# SW6106_Demo_board.net
KiCad netlist of a schematic drawn in Altium Designer
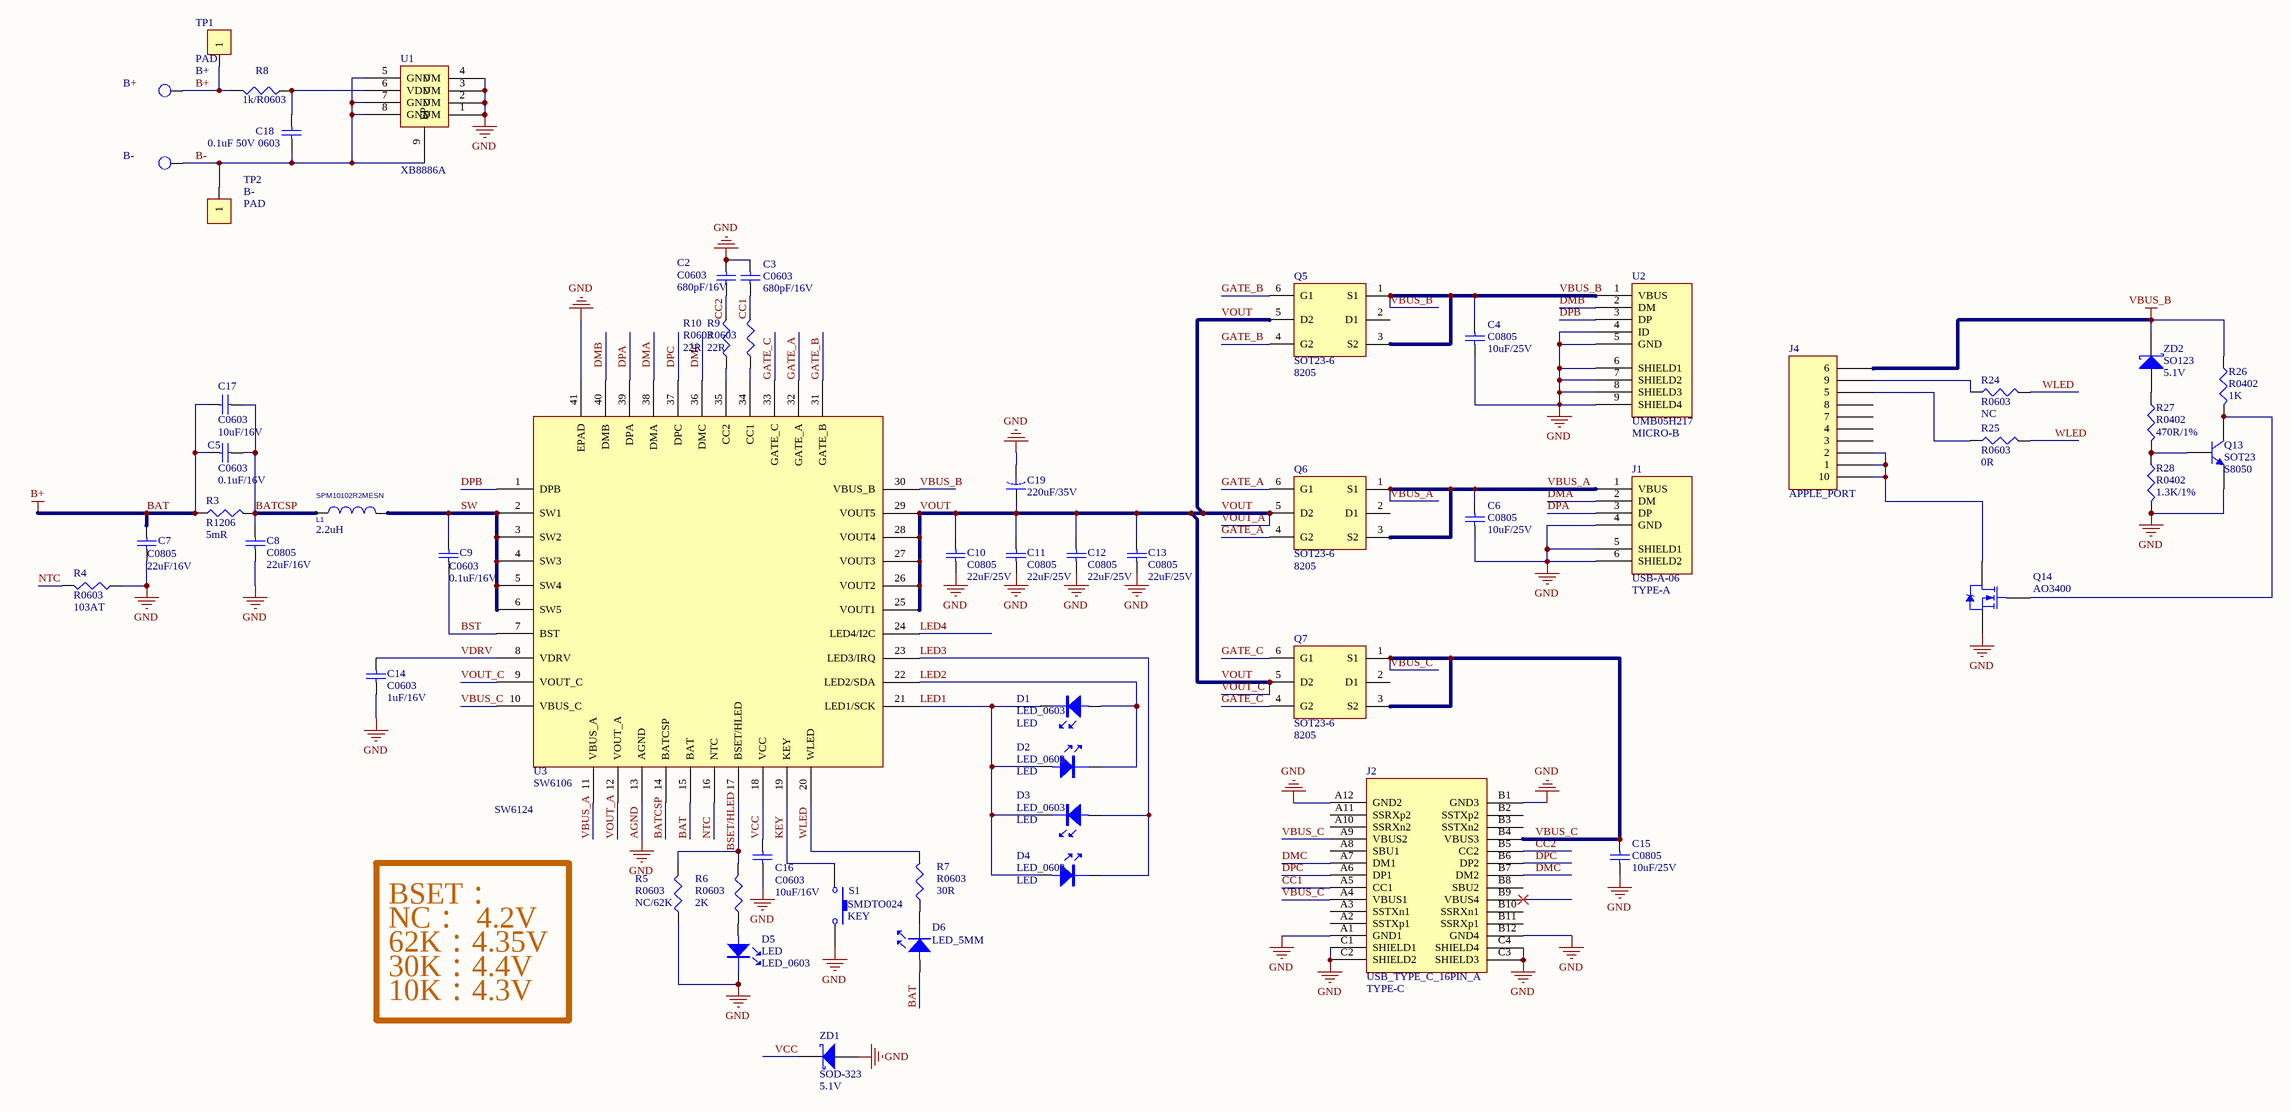
[diagram p0: SW6106 Demo board.SchDoc]

(export (version "E")
  (design (tool "Eeschema 10.0.6"))
  (components
    (comp (ref "B+") (value "PDA") (footprint "PAD") (libsource (lib "ZYX") (part "PDA")))
    (comp (ref "B-") (value "PDA") (footprint "PAD") (libsource (lib "ZYX") (part "PDA")))
    (comp (ref "C2")
      (value "C0603")
      (footprint "C0603")
      (description "Capacitor")
      (fields (field (name "ALTIUM_VALUE") "680pF/16V") (field (name "PUBLISHER") "Altium Limited"))
      (libsource (lib "*") (part "CAP0603"))
    )
    (comp (ref "C3")
      (value "C0603")
      (footprint "C0603")
      (description "Capacitor")
      (fields (field (name "ALTIUM_VALUE") "680pF/16V") (field (name "PUBLISHER") "Altium Limited"))
      (libsource (lib "*") (part "CAP0603"))
    )
    (comp (ref "C4")
      (value "C0805")
      (footprint "C0805")
      (description "Capacitor")
      (fields (field (name "ALTIUM_VALUE") "10uF/25V") (field (name "PUBLISHER") "Altium Limited"))
      (libsource (lib "*") (part "CAP0603"))
    )
    (comp (ref "C5")
      (value "C0603")
      (footprint "C0603")
      (description "Capacitor")
      (fields (field (name "ALTIUM_VALUE") "0.1uF/16V") (field (name "PUBLISHER") "Altium Limited"))
      (libsource (lib "*") (part "CAP0603"))
    )
    (comp (ref "C6")
      (value "C0805")
      (footprint "C0805")
      (description "Capacitor")
      (fields (field (name "ALTIUM_VALUE") "10uF/25V") (field (name "PUBLISHER") "Altium Limited"))
      (libsource (lib "*") (part "CAP0603"))
    )
    (comp (ref "C7")
      (value "C0805")
      (footprint "C0805")
      (description "Capacitor")
      (fields (field (name "ALTIUM_VALUE") "22uF/16V") (field (name "PUBLISHER") "Altium Limited"))
      (libsource (lib "*") (part "CAP0805"))
    )
    (comp (ref "C8")
      (value "C0805")
      (footprint "C0805")
      (description "Capacitor")
      (fields (field (name "ALTIUM_VALUE") "22uF/16V") (field (name "PUBLISHER") "Altium Limited"))
      (libsource (lib "*") (part "CAP0805"))
    )
    (comp (ref "C9")
      (value "C0603")
      (footprint "C0603")
      (description "Capacitor")
      (fields (field (name "ALTIUM_VALUE") "0.1uF/16V") (field (name "PUBLISHER") "Altium Limited"))
      (libsource (lib "*") (part "CAP0603"))
    )
    (comp (ref "C10")
      (value "C0805")
      (footprint "C0805")
      (description "Capacitor")
      (fields (field (name "ALTIUM_VALUE") "22uF/25V") (field (name "PUBLISHER") "Altium Limited"))
      (libsource (lib "*") (part "CAP0805"))
    )
    (comp (ref "C11")
      (value "C0805")
      (footprint "C0805")
      (description "Capacitor")
      (fields (field (name "ALTIUM_VALUE") "22uF/25V") (field (name "PUBLISHER") "Altium Limited"))
      (libsource (lib "*") (part "CAP0805"))
    )
    (comp (ref "C12")
      (value "C0805")
      (footprint "C0805")
      (description "Capacitor")
      (fields (field (name "ALTIUM_VALUE") "22uF/25V") (field (name "PUBLISHER") "Altium Limited"))
      (libsource (lib "*") (part "CAP0805"))
    )
    (comp (ref "C13")
      (value "C0805")
      (footprint "C0805")
      (description "Capacitor")
      (fields (field (name "ALTIUM_VALUE") "22uF/25V") (field (name "PUBLISHER") "Altium Limited"))
      (libsource (lib "*") (part "CAP0805"))
    )
    (comp (ref "C14")
      (value "C0603")
      (footprint "C0603")
      (description "Capacitor")
      (fields (field (name "ALTIUM_VALUE") "1uF/16V") (field (name "PUBLISHER") "Altium Limited"))
      (libsource (lib "*") (part "CAP0603"))
    )
    (comp (ref "C15")
      (value "C0805")
      (footprint "C0805")
      (description "Capacitor")
      (fields (field (name "ALTIUM_VALUE") "10uF/25V") (field (name "PUBLISHER") "Altium Limited"))
      (libsource (lib "*") (part "CAP0603"))
    )
    (comp (ref "C16")
      (value "C0603")
      (footprint "C0603")
      (description "Capacitor")
      (fields (field (name "ALTIUM_VALUE") "10uF/16V") (field (name "PUBLISHER") "Altium Limited"))
      (libsource (lib "*") (part "CAP0603"))
    )
    (comp (ref "C17")
      (value "C0603")
      (footprint "C0603")
      (description "Capacitor")
      (fields (field (name "ALTIUM_VALUE") "10uF/16V") (field (name "PUBLISHER") "Altium Limited"))
      (libsource (lib "*") (part "CAP0603"))
    )
    (comp (ref "C18") (value "0.1uF 50V 0603") (footprint "LIB:C0402") (libsource (lib "ZYX") (part "Cap")))
    (comp (ref "C19")
      (value "220uF/35V")
      (footprint "Cap  ( E )  6.5 * 12.0  Erect")
      (description "Electroytic Capacitor, 100uF/35V, ±20%, 105℃，Φ 6.5 * 12.0 mm")
      (fields (field (name "Comment") "E - Cap") (field (name "PUBLISHER") "Altium Limited"))
      (libsource (lib "D-lib") (part "E - Cap"))
    )
    (comp (ref "D1") (value "LED") (footprint "LED_0603") (libsource (lib "*") (part "LED")))
    (comp (ref "D2") (value "LED") (footprint "LED_0603") (libsource (lib "*") (part "LED")))
    (comp (ref "D3") (value "LED") (footprint "LED_0603") (libsource (lib "*") (part "LED")))
    (comp (ref "D4") (value "LED") (footprint "LED_0603") (libsource (lib "*") (part "LED")))
    (comp (ref "D5") (value "LED") (footprint "LED_0603") (libsource (lib "*") (part "LED")))
    (comp (ref "D6")
      (value "LED_5MM")
      (footprint "LED_5MM")
      (fields (field (name "FOOTPRINF") "LED_5MM"))
      (libsource (lib "*") (part "LED"))
    )
    (comp (ref "J1")
      (value "TYPE-A")
      (footprint "USB-A-06")
      (fields (field (name "FOOTPRINF") "USB-A-06") (field (name "Comment") "TYPE-A-1"))
      (libsource (lib "*") (part "TYPE-A-1"))
    )
    (comp (ref "J2") (value "TYPE-C") (footprint "USB_TYPE_C_16PIN_A") (libsource (lib "*") (part "TYPE-C")))
    (comp (ref "J4")
      (value "APPLE_PORT")
      (footprint "Lightning")
      (libsource (lib "TEST") (part "APPLE_PORT"))
    )
    (comp (ref "L1")
      (value "SPM10102R2MESN")
      (footprint "INDUCTOR_SPM1010")
      (fields (field (name "ALTIUM_VALUE") "2.2uH"))
      (libsource (lib "*") (part "INDUCTOR"))
    )
    (comp (ref "Q5")
      (value "8205")
      (footprint "SOT23-6")
      (fields (field (name "FOOTPRINF") "SOT23-6"))
      (libsource (lib "*") (part "8205B"))
    )
    (comp (ref "Q6")
      (value "8205")
      (footprint "SOT23-6")
      (fields (field (name "FOOTPRINF") "SOT23-6"))
      (libsource (lib "*") (part "8205B"))
    )
    (comp (ref "Q7")
      (value "8205")
      (footprint "SOT23-6")
      (fields (field (name "FOOTPRINF") "SOT23-6"))
      (libsource (lib "*") (part "8205B"))
    )
    (comp (ref "Q13")
      (value "S8050")
      (footprint "SOT23")
      (description "NPN General Purpose Amplifier")
      (fields (field (name "PUBLISHER") "Altium Limited"))
      (libsource (lib "Miscellaneous Devices") (part "2N3904"))
    )
    (comp (ref "Q14")
      (value "AO3400")
      (footprint "SOT-23-3")
      (description "N-Channel Power MOSFET")
      (fields (field (name "Comment") "NMOS-2") (field (name "PUBLISHER") "Altium Limited"))
      (libsource (lib "D-lib") (part "NMOS-2"))
    )
    (comp (ref "R3")
      (value "R1206")
      (footprint "R1206")
      (description "Resistor")
      (fields (field (name "ALTIUM_VALUE") "5mR") (field (name "PUBLISHER") "Altium Limited"))
      (libsource (lib "*") (part "RES"))
    )
    (comp (ref "R4")
      (value "R0603")
      (footprint "R0603")
      (description "Resistor")
      (fields (field (name "ALTIUM_VALUE") "103AT") (field (name "PUBLISHER") "Altium Limited"))
      (libsource (lib "*") (part "RES"))
    )
    (comp (ref "R5")
      (value "R0603")
      (footprint "R0603")
      (description "Resistor")
      (fields (field (name "ALTIUM_VALUE") "NC/62K") (field (name "PUBLISHER") "Altium Limited"))
      (libsource (lib "*") (part "RES"))
    )
    (comp (ref "R6")
      (value "R0603")
      (footprint "R0603")
      (description "Resistor")
      (fields (field (name "ALTIUM_VALUE") "2K") (field (name "PUBLISHER") "Altium Limited"))
      (libsource (lib "*") (part "RES"))
    )
    (comp (ref "R7")
      (value "R0603")
      (footprint "R0603")
      (description "Resistor")
      (fields (field (name "ALTIUM_VALUE") "30R") (field (name "PUBLISHER") "Altium Limited"))
      (libsource (lib "*") (part "RES"))
    )
    (comp (ref "R8")
      (value "1k/R0603")
      (footprint "R0402")
      (description "Resistor")
      (fields (field (name "PUBLISHER") "Altium Limited"))
      (libsource (lib "*") (part "RES"))
    )
    (comp (ref "R9")
      (value "R0603")
      (footprint "R0603")
      (description "Resistor")
      (fields (field (name "ALTIUM_VALUE") "22R") (field (name "PUBLISHER") "Altium Limited"))
      (libsource (lib "*") (part "RES"))
    )
    (comp (ref "R10")
      (value "R0603")
      (footprint "R0603")
      (description "Resistor")
      (fields (field (name "ALTIUM_VALUE") "22R") (field (name "PUBLISHER") "Altium Limited"))
      (libsource (lib "*") (part "RES"))
    )
    (comp (ref "R24")
      (value "R0603")
      (footprint "R0402")
      (description "Resistor")
      (fields (field (name "ALTIUM_VALUE") "NC") (field (name "PUBLISHER") "Altium Limited"))
      (libsource (lib "*") (part "RES"))
    )
    (comp (ref "R25")
      (value "R0603")
      (footprint "R0402")
      (description "Resistor")
      (fields (field (name "ALTIUM_VALUE") "0R") (field (name "PUBLISHER") "Altium Limited"))
      (libsource (lib "*") (part "RES"))
    )
    (comp (ref "R26")
      (value "R0402")
      (footprint "R0402")
      (description "Resistor")
      (fields (field (name "ALTIUM_VALUE") "1K") (field (name "PUBLISHER") "Altium Limited"))
      (libsource (lib "Miscellaneous Devices") (part "Res3"))
    )
    (comp (ref "R27")
      (value "R0402")
      (footprint "R0402")
      (description "Resistor")
      (fields (field (name "ALTIUM_VALUE") "470R/1%") (field (name "PUBLISHER") "Altium Limited"))
      (libsource (lib "Miscellaneous Devices") (part "Res3"))
    )
    (comp (ref "R28")
      (value "R0402")
      (footprint "R0402")
      (description "Resistor")
      (fields (field (name "ALTIUM_VALUE") "1.3K/1%") (field (name "PUBLISHER") "Altium Limited"))
      (libsource (lib "Miscellaneous Devices") (part "Res3"))
    )
    (comp (ref "S1")
      (value "KEY")
      (footprint "SMDTO024")
      (fields (field (name "FOOTPRINF") "SMDTO024"))
      (libsource (lib "*") (part "SW K"))
    )
    (comp (ref "TP1") (value "B+") (footprint "PAD") (libsource (lib "*") (part "Test Point")))
    (comp (ref "TP2") (value "B-") (footprint "PAD") (libsource (lib "") (part "Test Point_1")))
    (comp (ref "U1") (value "XB8886A") (footprint "SOP-8-G") (libsource (lib "ZYX") (part "XB8089")))
    (comp (ref "U2")
      (value "MICRO-B")
      (footprint "UMB05H217")
      (fields (field (name "FOOTPRINTF") "UMB05H217") (field (name "Comment") "USB_MICRO_B"))
      (libsource (lib "*") (part "USB_MICRO_B"))
    )
    (comp (ref "U3")
      (value "SW6106")
      (footprint "QFN40_EPAD_SW6124_6X6")
      (fields (field (name "ALTIUM_VALUE") "SW6124"))
      (libsource (lib "*") (part "SW6124"))
    )
    (comp (ref "ZD1")
      (value "SOD-323")
      (footprint "SOD-123")
      (description "Schottky Rectifier")
      (fields (field (name "ALTIUM_UNNAMED_1") "5.1V") (field (name "PUBLISHER") "Altium Limited"))
      (libsource (lib "Miscellaneous Devices") (part "Diode 11DQ03"))
    )
    (comp (ref "ZD2")
      (value "5.1V")
      (footprint "SO123")
      (description "Schottky Rectifier")
      (fields (field (name "PUBLISHER") "Altium Limited"))
      (libsource (lib "Miscellaneous Devices") (part "Diode 10TQ035"))
    )
  )
  (nets
    (net (code "1") (name "/B-") (class "Default")
      (node (ref "B-") (pin "0") (pintype "passive"))
      (node (ref "C18") (pin "1") (pinfunction "1_1") (pintype "passive"))
      (node (ref "TP2") (pin "1") (pinfunction "1_1") (pintype "passive"))
      (node (ref "U1") (pin "5") (pinfunction "GND_5") (pintype "passive"))
      (node (ref "U1") (pin "7") (pinfunction "GND_7") (pintype "passive"))
      (node (ref "U1") (pin "8") (pinfunction "GND_8") (pintype "passive"))
      (node (ref "U1") (pin "9") (pinfunction "EP_9") (pintype "passive"))
    )
    (net (code "2") (name "/BATCSP") (class "Default")
      (node (ref "C17") (pin "1") (pinfunction "1_1") (pintype "passive"))
      (node (ref "C5") (pin "2") (pinfunction "2_2") (pintype "passive"))
      (node (ref "C8") (pin "2") (pinfunction "2_2") (pintype "passive"))
      (node (ref "L1") (pin "1") (pinfunction "1_1") (pintype "passive"))
      (node (ref "R3") (pin "2") (pinfunction "2_2") (pintype "passive"))
      (node (ref "U3") (pin "14") (pinfunction "BATCSP_14") (pintype "passive"))
    )
    (net (code "3") (name "/BSET{slash}HLED") (class "Default")
      (node (ref "R5") (pin "2") (pinfunction "2_2") (pintype "passive"))
      (node (ref "R6") (pin "2") (pinfunction "2_2") (pintype "passive"))
      (node (ref "U3") (pin "17") (pinfunction "BSET/HLED_17") (pintype "passive"))
    )
    (net (code "4") (name "/BST") (class "Default")
      (node (ref "C9") (pin "1") (pinfunction "1_1") (pintype "passive"))
      (node (ref "U3") (pin "7") (pinfunction "BST_7") (pintype "passive"))
    )
    (net (code "5") (name "/CC1") (class "Default")
      (node (ref "J2") (pin "A5") (pinfunction "CC1_A5") (pintype "passive"))
    )
    (net (code "6") (name "/CC2") (class "Default")
      (node (ref "J2") (pin "B5") (pinfunction "CC2_B5") (pintype "passive"))
    )
    (net (code "7") (name "/DMA") (class "Default")
      (node (ref "J1") (pin "2") (pinfunction "DM_2") (pintype "passive"))
      (node (ref "U3") (pin "38") (pinfunction "DMA_38") (pintype "passive"))
    )
    (net (code "8") (name "/DMB") (class "Default")
      (node (ref "U2") (pin "2") (pinfunction "DM_2") (pintype "passive"))
      (node (ref "U3") (pin "40") (pinfunction "DMB_40") (pintype "passive"))
    )
    (net (code "9") (name "/DMC") (class "Default")
      (node (ref "J2") (pin "A7") (pinfunction "DM1_A7") (pintype "passive"))
      (node (ref "J2") (pin "B7") (pinfunction "DM2_B7") (pintype "passive"))
      (node (ref "U3") (pin "36") (pinfunction "DMC_36") (pintype "passive"))
    )
    (net (code "10") (name "/DPA") (class "Default")
      (node (ref "J1") (pin "3") (pinfunction "DP_3") (pintype "passive"))
      (node (ref "U3") (pin "39") (pinfunction "DPA_39") (pintype "passive"))
    )
    (net (code "11") (name "/DPB") (class "Default")
      (node (ref "U2") (pin "3") (pinfunction "DP_3") (pintype "passive"))
      (node (ref "U3") (pin "1") (pinfunction "DPB_1") (pintype "passive"))
    )
    (net (code "12") (name "/DPC") (class "Default")
      (node (ref "J2") (pin "A6") (pinfunction "DP1_A6") (pintype "passive"))
      (node (ref "J2") (pin "B6") (pinfunction "DP2_B6") (pintype "passive"))
      (node (ref "U3") (pin "37") (pinfunction "DPC_37") (pintype "passive"))
    )
    (net (code "13") (name "/GATE_A") (class "Default")
      (node (ref "Q6") (pin "4") (pinfunction "G2_4") (pintype "passive"))
      (node (ref "Q6") (pin "6") (pinfunction "G1_6") (pintype "passive"))
      (node (ref "U3") (pin "32") (pinfunction "GATE_A_32") (pintype "passive"))
    )
    (net (code "14") (name "/GATE_B") (class "Default")
      (node (ref "Q5") (pin "4") (pinfunction "G2_4") (pintype "passive"))
      (node (ref "Q5") (pin "6") (pinfunction "G1_6") (pintype "passive"))
      (node (ref "U3") (pin "31") (pinfunction "GATE_B_31") (pintype "passive"))
    )
    (net (code "15") (name "/GATE_C") (class "Default")
      (node (ref "Q7") (pin "4") (pinfunction "G2_4") (pintype "passive"))
      (node (ref "Q7") (pin "6") (pinfunction "G1_6") (pintype "passive"))
      (node (ref "U3") (pin "33") (pinfunction "GATE_C_33") (pintype "passive"))
    )
    (net (code "16") (name "/KEY") (class "Default")
      (node (ref "S1") (pin "1") (pinfunction "1_1") (pintype "passive"))
      (node (ref "U3") (pin "19") (pinfunction "KEY_19") (pintype "passive"))
    )
    (net (code "17") (name "/LED1") (class "Default")
      (node (ref "D1") (pin "2") (pinfunction "K_2") (pintype "passive"))
      (node (ref "D2") (pin "1") (pinfunction "A_1") (pintype "passive"))
      (node (ref "D3") (pin "2") (pinfunction "K_2") (pintype "passive"))
      (node (ref "D4") (pin "1") (pinfunction "A_1") (pintype "passive"))
      (node (ref "U3") (pin "21") (pinfunction "LED1/SCK_21") (pintype "passive"))
    )
    (net (code "18") (name "/LED2") (class "Default")
      (node (ref "D1") (pin "1") (pinfunction "A_1") (pintype "passive"))
      (node (ref "D2") (pin "2") (pinfunction "K_2") (pintype "passive"))
      (node (ref "U3") (pin "22") (pinfunction "LED2/SDA_22") (pintype "passive"))
    )
    (net (code "19") (name "/LED3") (class "Default")
      (node (ref "D3") (pin "1") (pinfunction "A_1") (pintype "passive"))
      (node (ref "D4") (pin "2") (pinfunction "K_2") (pintype "passive"))
      (node (ref "U3") (pin "23") (pinfunction "LED3/IRQ_23") (pintype "passive"))
    )
    (net (code "20") (name "/LED4") (class "Default")
      (node (ref "U3") (pin "24") (pinfunction "LED4/I2C_24") (pintype "passive"))
    )
    (net (code "21") (name "/NTC") (class "Default")
      (node (ref "R4") (pin "2") (pinfunction "2_2") (pintype "passive"))
      (node (ref "U3") (pin "16") (pinfunction "NTC_16") (pintype "passive"))
    )
    (net (code "22") (name "/SW") (class "Default")
      (node (ref "C9") (pin "2") (pinfunction "2_2") (pintype "passive"))
      (node (ref "L1") (pin "2") (pinfunction "2_2") (pintype "passive"))
      (node (ref "U3") (pin "2") (pinfunction "SW1_2") (pintype "passive"))
      (node (ref "U3") (pin "3") (pinfunction "SW2_3") (pintype "passive"))
      (node (ref "U3") (pin "4") (pinfunction "SW3_4") (pintype "passive"))
      (node (ref "U3") (pin "5") (pinfunction "SW4_5") (pintype "passive"))
      (node (ref "U3") (pin "6") (pinfunction "SW5_6") (pintype "passive"))
    )
    (net (code "23") (name "/VBUS_A") (class "Default")
      (node (ref "C6") (pin "2") (pinfunction "2_2") (pintype "passive"))
      (node (ref "J1") (pin "1") (pinfunction "VBUS_1") (pintype "passive"))
      (node (ref "Q6") (pin "1") (pinfunction "S1_1") (pintype "passive"))
      (node (ref "Q6") (pin "3") (pinfunction "S2_3") (pintype "passive"))
      (node (ref "U3") (pin "11") (pinfunction "VBUS_A_11") (pintype "passive"))
    )
    (net (code "24") (name "/VBUS_C") (class "Default")
      (node (ref "C15") (pin "2") (pinfunction "2_2") (pintype "passive"))
      (node (ref "J2") (pin "A4") (pinfunction "VBUS1_A4") (pintype "passive"))
      (node (ref "J2") (pin "A9") (pinfunction "VBUS2_A9") (pintype "passive"))
      (node (ref "J2") (pin "B4") (pinfunction "VBUS3_B4") (pintype "passive"))
      (node (ref "Q7") (pin "1") (pinfunction "S1_1") (pintype "passive"))
      (node (ref "Q7") (pin "3") (pinfunction "S2_3") (pintype "passive"))
      (node (ref "U3") (pin "10") (pinfunction "VBUS_C_10") (pintype "passive"))
    )
    (net (code "25") (name "/VCC") (class "Default")
      (node (ref "C16") (pin "2") (pinfunction "2_2") (pintype "passive"))
      (node (ref "U3") (pin "18") (pinfunction "VCC_18") (pintype "passive"))
      (node (ref "ZD1") (pin "2") (pinfunction "K_2") (pintype "passive"))
    )
    (net (code "26") (name "/VDRV") (class "Default")
      (node (ref "C14") (pin "2") (pinfunction "2_2") (pintype "passive"))
      (node (ref "U3") (pin "8") (pinfunction "VDRV_8") (pintype "passive"))
    )
    (net (code "27") (name "/VOUT") (class "Default")
      (node (ref "C10") (pin "2") (pinfunction "2_2") (pintype "passive"))
      (node (ref "C11") (pin "2") (pinfunction "2_2") (pintype "passive"))
      (node (ref "C12") (pin "2") (pinfunction "2_2") (pintype "passive"))
      (node (ref "C13") (pin "2") (pinfunction "2_2") (pintype "passive"))
      (node (ref "C19") (pin "1") (pinfunction "1_1") (pintype "passive"))
      (node (ref "Q5") (pin "5") (pinfunction "D2_5") (pintype "passive"))
      (node (ref "Q6") (pin "5") (pinfunction "D2_5") (pintype "passive"))
      (node (ref "Q7") (pin "5") (pinfunction "D2_5") (pintype "passive"))
      (node (ref "U3") (pin "12") (pinfunction "VOUT_A_12") (pintype "passive"))
      (node (ref "U3") (pin "25") (pinfunction "VOUT1_25") (pintype "passive"))
      (node (ref "U3") (pin "26") (pinfunction "VOUT2_26") (pintype "passive"))
      (node (ref "U3") (pin "27") (pinfunction "VOUT3_27") (pintype "passive"))
      (node (ref "U3") (pin "28") (pinfunction "VOUT4_28") (pintype "passive"))
      (node (ref "U3") (pin "29") (pinfunction "VOUT5_29") (pintype "passive"))
      (node (ref "U3") (pin "9") (pinfunction "VOUT_C_9") (pintype "passive"))
    )
    (net (code "28") (name "/WLED") (class "Default")
      (node (ref "R24") (pin "2") (pinfunction "2_2") (pintype "passive"))
      (node (ref "R25") (pin "2") (pinfunction "2_2") (pintype "passive"))
      (node (ref "R7") (pin "2") (pinfunction "2_2") (pintype "passive"))
      (node (ref "U3") (pin "20") (pinfunction "WLED_20") (pintype "passive"))
    )
    (net (code "29") (name "B+") (class "Default")
      (node (ref "B+") (pin "0") (pintype "passive"))
      (node (ref "C17") (pin "2") (pinfunction "2_2") (pintype "passive"))
      (node (ref "C5") (pin "1") (pinfunction "1_1") (pintype "passive"))
      (node (ref "C7") (pin "2") (pinfunction "2_2") (pintype "passive"))
      (node (ref "D6") (pin "1") (pinfunction "A_1") (pintype "passive"))
      (node (ref "R3") (pin "1") (pinfunction "1_1") (pintype "passive"))
      (node (ref "R8") (pin "2") (pinfunction "2_2") (pintype "passive"))
      (node (ref "TP1") (pin "1") (pinfunction "1_1") (pintype "passive"))
      (node (ref "U3") (pin "15") (pinfunction "BAT_15") (pintype "passive"))
    )
    (net (code "30") (name "GND") (class "Default")
      (node (ref "C10") (pin "1") (pinfunction "1_1") (pintype "passive"))
      (node (ref "C11") (pin "1") (pinfunction "1_1") (pintype "passive"))
      (node (ref "C12") (pin "1") (pinfunction "1_1") (pintype "passive"))
      (node (ref "C13") (pin "1") (pinfunction "1_1") (pintype "passive"))
      (node (ref "C14") (pin "1") (pinfunction "1_1") (pintype "passive"))
      (node (ref "C15") (pin "1") (pinfunction "1_1") (pintype "passive"))
      (node (ref "C16") (pin "1") (pinfunction "1_1") (pintype "passive"))
      (node (ref "C19") (pin "2") (pinfunction "2_2") (pintype "passive"))
      (node (ref "C2") (pin "2") (pinfunction "2_2") (pintype "passive"))
      (node (ref "C3") (pin "2") (pinfunction "2_2") (pintype "passive"))
      (node (ref "C4") (pin "1") (pinfunction "1_1") (pintype "passive"))
      (node (ref "C6") (pin "1") (pinfunction "1_1") (pintype "passive"))
      (node (ref "C7") (pin "1") (pinfunction "1_1") (pintype "passive"))
      (node (ref "C8") (pin "1") (pinfunction "1_1") (pintype "passive"))
      (node (ref "D5") (pin "2") (pinfunction "K_2") (pintype "passive"))
      (node (ref "J1") (pin "4") (pinfunction "GND_4") (pintype "passive"))
      (node (ref "J1") (pin "5") (pinfunction "SHIELD1_5") (pintype "passive"))
      (node (ref "J1") (pin "6") (pinfunction "SHIELD2_6") (pintype "passive"))
      (node (ref "J2") (pin "A1") (pinfunction "GND1_A1") (pintype "passive"))
      (node (ref "J2") (pin "A12") (pinfunction "GND2_A12") (pintype "passive"))
      (node (ref "J2") (pin "B1") (pinfunction "GND3_B1") (pintype "passive"))
      (node (ref "J2") (pin "B12") (pinfunction "GND4_B12") (pintype "passive"))
      (node (ref "J2") (pin "C1") (pinfunction "SHIELD1_C1") (pintype "passive"))
      (node (ref "J2") (pin "C2") (pinfunction "SHIELD2_C2") (pintype "passive"))
      (node (ref "J2") (pin "C3") (pinfunction "SHIELD3_C3") (pintype "passive"))
      (node (ref "J2") (pin "C4") (pinfunction "SHIELD4_C4") (pintype "passive"))
      (node (ref "Q13") (pin "2") (pinfunction "E_2") (pintype "passive"))
      (node (ref "Q14") (pin "2") (pinfunction "S_2") (pintype "passive"))
      (node (ref "R28") (pin "2") (pinfunction "2_2") (pintype "passive"))
      (node (ref "R4") (pin "1") (pinfunction "1_1") (pintype "passive"))
      (node (ref "R5") (pin "1") (pinfunction "1_1") (pintype "passive"))
      (node (ref "S1") (pin "2") (pinfunction "2_2") (pintype "passive"))
      (node (ref "U1") (pin "1") (pinfunction "VM_1") (pintype "passive"))
      (node (ref "U1") (pin "2") (pinfunction "VM_2") (pintype "passive"))
      (node (ref "U1") (pin "3") (pinfunction "VM_3") (pintype "passive"))
      (node (ref "U1") (pin "4") (pinfunction "VM_4") (pintype "passive"))
      (node (ref "U2") (pin "4") (pinfunction "ID_4") (pintype "passive"))
      (node (ref "U2") (pin "5") (pinfunction "GND_5") (pintype "passive"))
      (node (ref "U2") (pin "6") (pinfunction "SHIELD1_6") (pintype "passive"))
      (node (ref "U2") (pin "7") (pinfunction "SHIELD2_7") (pintype "passive"))
      (node (ref "U2") (pin "8") (pinfunction "SHIELD3_8") (pintype "passive"))
      (node (ref "U2") (pin "9") (pinfunction "SHIELD4_9") (pintype "passive"))
      (node (ref "U3") (pin "13") (pinfunction "AGND_13") (pintype "passive"))
      (node (ref "U3") (pin "41") (pinfunction "EPAD_41") (pintype "passive"))
      (node (ref "ZD1") (pin "1") (pinfunction "A_1") (pintype "passive"))
    )
    (net (code "31") (name "Net-(C2-Pad1)") (class "Default")
      (node (ref "C2") (pin "1") (pinfunction "1_1") (pintype "passive"))
      (node (ref "R10") (pin "2") (pinfunction "2_2") (pintype "passive"))
    )
    (net (code "32") (name "Net-(C3-Pad1)") (class "Default")
      (node (ref "C3") (pin "1") (pinfunction "1_1") (pintype "passive"))
      (node (ref "R9") (pin "2") (pinfunction "2_2") (pintype "passive"))
    )
    (net (code "33") (name "Net-(D5-A)") (class "Default")
      (node (ref "D5") (pin "1") (pinfunction "A_1") (pintype "passive"))
      (node (ref "R6") (pin "1") (pinfunction "1_1") (pintype "passive"))
    )
    (net (code "34") (name "Net-(D6-K)") (class "Default")
      (node (ref "D6") (pin "2") (pinfunction "K_2") (pintype "passive"))
      (node (ref "R7") (pin "1") (pinfunction "1_1") (pintype "passive"))
    )
    (net (code "35") (name "Net-(J4-Pad5)") (class "Default")
      (node (ref "J4") (pin "5") (pinfunction "5_5") (pintype "passive"))
      (node (ref "R25") (pin "1") (pinfunction "1_1") (pintype "passive"))
    )
    (net (code "36") (name "Net-(J4-Pad9)") (class "Default")
      (node (ref "J4") (pin "9") (pinfunction "9_9") (pintype "passive"))
      (node (ref "R24") (pin "1") (pinfunction "1_1") (pintype "passive"))
    )
    (net (code "37") (name "Net-(Q13-B)") (class "Default")
      (node (ref "Q13") (pin "1") (pinfunction "B_1") (pintype "passive"))
      (node (ref "R27") (pin "2") (pinfunction "2_2") (pintype "passive"))
      (node (ref "R28") (pin "1") (pinfunction "1_1") (pintype "passive"))
    )
    (net (code "38") (name "Net-(Q13-C)") (class "Default")
      (node (ref "Q13") (pin "3") (pinfunction "C_3") (pintype "passive"))
      (node (ref "Q14") (pin "1") (pinfunction "G_1") (pintype "passive"))
      (node (ref "R26") (pin "2") (pinfunction "2_2") (pintype "passive"))
    )
    (net (code "39") (name "Net-(Q14-D)") (class "Default")
      (node (ref "J4") (pin "1") (pinfunction "1_1") (pintype "passive"))
      (node (ref "J4") (pin "10") (pinfunction "10_10") (pintype "passive"))
      (node (ref "J4") (pin "2") (pinfunction "2_2") (pintype "passive"))
      (node (ref "Q14") (pin "3") (pinfunction "D_3") (pintype "passive"))
    )
    (net (code "40") (name "Net-(U1-VDD)") (class "Default")
      (node (ref "C18") (pin "0") (pinfunction "0_0") (pintype "passive"))
      (node (ref "R8") (pin "1") (pinfunction "1_1") (pintype "passive"))
      (node (ref "U1") (pin "6") (pinfunction "VDD_6") (pintype "passive"))
    )
    (net (code "41") (name "Net-(U3-CC1)") (class "Default")
      (node (ref "R9") (pin "1") (pinfunction "1_1") (pintype "passive"))
      (node (ref "U3") (pin "34") (pinfunction "CC1_34") (pintype "passive"))
    )
    (net (code "42") (name "Net-(U3-CC2)") (class "Default")
      (node (ref "R10") (pin "1") (pinfunction "1_1") (pintype "passive"))
      (node (ref "U3") (pin "35") (pinfunction "CC2_35") (pintype "passive"))
    )
    (net (code "43") (name "Net-(ZD2-A)") (class "Default")
      (node (ref "R27") (pin "1") (pinfunction "1_1") (pintype "passive"))
      (node (ref "ZD2") (pin "3") (pinfunction "A_3") (pintype "passive"))
    )
    (net (code "44") (name "VBUS_B") (class "Default")
      (node (ref "C4") (pin "2") (pinfunction "2_2") (pintype "passive"))
      (node (ref "J4") (pin "6") (pinfunction "6_6") (pintype "passive"))
      (node (ref "Q5") (pin "1") (pinfunction "S1_1") (pintype "passive"))
      (node (ref "Q5") (pin "3") (pinfunction "S2_3") (pintype "passive"))
      (node (ref "R26") (pin "1") (pinfunction "1_1") (pintype "passive"))
      (node (ref "U2") (pin "1") (pinfunction "VBUS_1") (pintype "passive"))
      (node (ref "U3") (pin "30") (pinfunction "VBUS_B_30") (pintype "passive"))
      (node (ref "ZD2") (pin "1") (pinfunction "K_1") (pintype "passive"))
    )
    (net (code "45") (name "unconnected-(J2-SBU1-PadA8)") (class "Default")
      (node (ref "J2") (pin "A8") (pinfunction "SBU1_A8") (pintype "passive"))
    )
    (net (code "46") (name "unconnected-(J2-SBU2-PadB8)") (class "Default")
      (node (ref "J2") (pin "B8") (pinfunction "SBU2_B8") (pintype "passive"))
    )
    (net (code "47") (name "unconnected-(J2-SSRXn1-PadB10)") (class "Default")
      (node (ref "J2") (pin "B10") (pinfunction "SSRXn1_B10") (pintype "passive"))
    )
    (net (code "48") (name "unconnected-(J2-SSRXn2-PadA10)") (class "Default")
      (node (ref "J2") (pin "A10") (pinfunction "SSRXn2_A10") (pintype "passive"))
    )
    (net (code "49") (name "unconnected-(J2-SSRXp1-PadB11)") (class "Default")
      (node (ref "J2") (pin "B11") (pinfunction "SSRXp1_B11") (pintype "passive"))
    )
    (net (code "50") (name "unconnected-(J2-SSRXp2-PadA11)") (class "Default")
      (node (ref "J2") (pin "A11") (pinfunction "SSRXp2_A11") (pintype "passive"))
    )
    (net (code "51") (name "unconnected-(J2-SSTXn1-PadA3)") (class "Default")
      (node (ref "J2") (pin "A3") (pinfunction "SSTXn1_A3") (pintype "passive"))
    )
    (net (code "52") (name "unconnected-(J2-SSTXn2-PadB3)") (class "Default")
      (node (ref "J2") (pin "B3") (pinfunction "SSTXn2_B3") (pintype "passive"))
    )
    (net (code "53") (name "unconnected-(J2-SSTXp1-PadA2)") (class "Default")
      (node (ref "J2") (pin "A2") (pinfunction "SSTXp1_A2") (pintype "passive"))
    )
    (net (code "54") (name "unconnected-(J2-SSTXp2-PadB2)") (class "Default")
      (node (ref "J2") (pin "B2") (pinfunction "SSTXp2_B2") (pintype "passive"))
    )
    (net (code "55") (name "unconnected-(J2-VBUS4-PadB9)") (class "Default")
      (node (ref "J2") (pin "B9") (pinfunction "VBUS4_B9") (pintype "passive+no_connect"))
    )
    (net (code "56") (name "unconnected-(J4-Pad3)") (class "Default")
      (node (ref "J4") (pin "3") (pinfunction "3_3") (pintype "passive"))
    )
    (net (code "57") (name "unconnected-(J4-Pad4)") (class "Default")
      (node (ref "J4") (pin "4") (pinfunction "4_4") (pintype "passive"))
    )
    (net (code "58") (name "unconnected-(J4-Pad7)") (class "Default")
      (node (ref "J4") (pin "7") (pinfunction "7_7") (pintype "passive"))
    )
    (net (code "59") (name "unconnected-(J4-Pad8)") (class "Default")
      (node (ref "J4") (pin "8") (pinfunction "8_8") (pintype "passive"))
    )
    (net (code "60") (name "unconnected-(Q5-D1-Pad2)") (class "Default")
      (node (ref "Q5") (pin "2") (pinfunction "D1_2") (pintype "passive"))
    )
    (net (code "61") (name "unconnected-(Q6-D1-Pad2)") (class "Default")
      (node (ref "Q6") (pin "2") (pinfunction "D1_2") (pintype "passive"))
    )
    (net (code "62") (name "unconnected-(Q7-D1-Pad2)") (class "Default")
      (node (ref "Q7") (pin "2") (pinfunction "D1_2") (pintype "passive"))
    )
  )
)
